# JTAG.net
KiCad netlist of a schematic drawn in Altium Designer
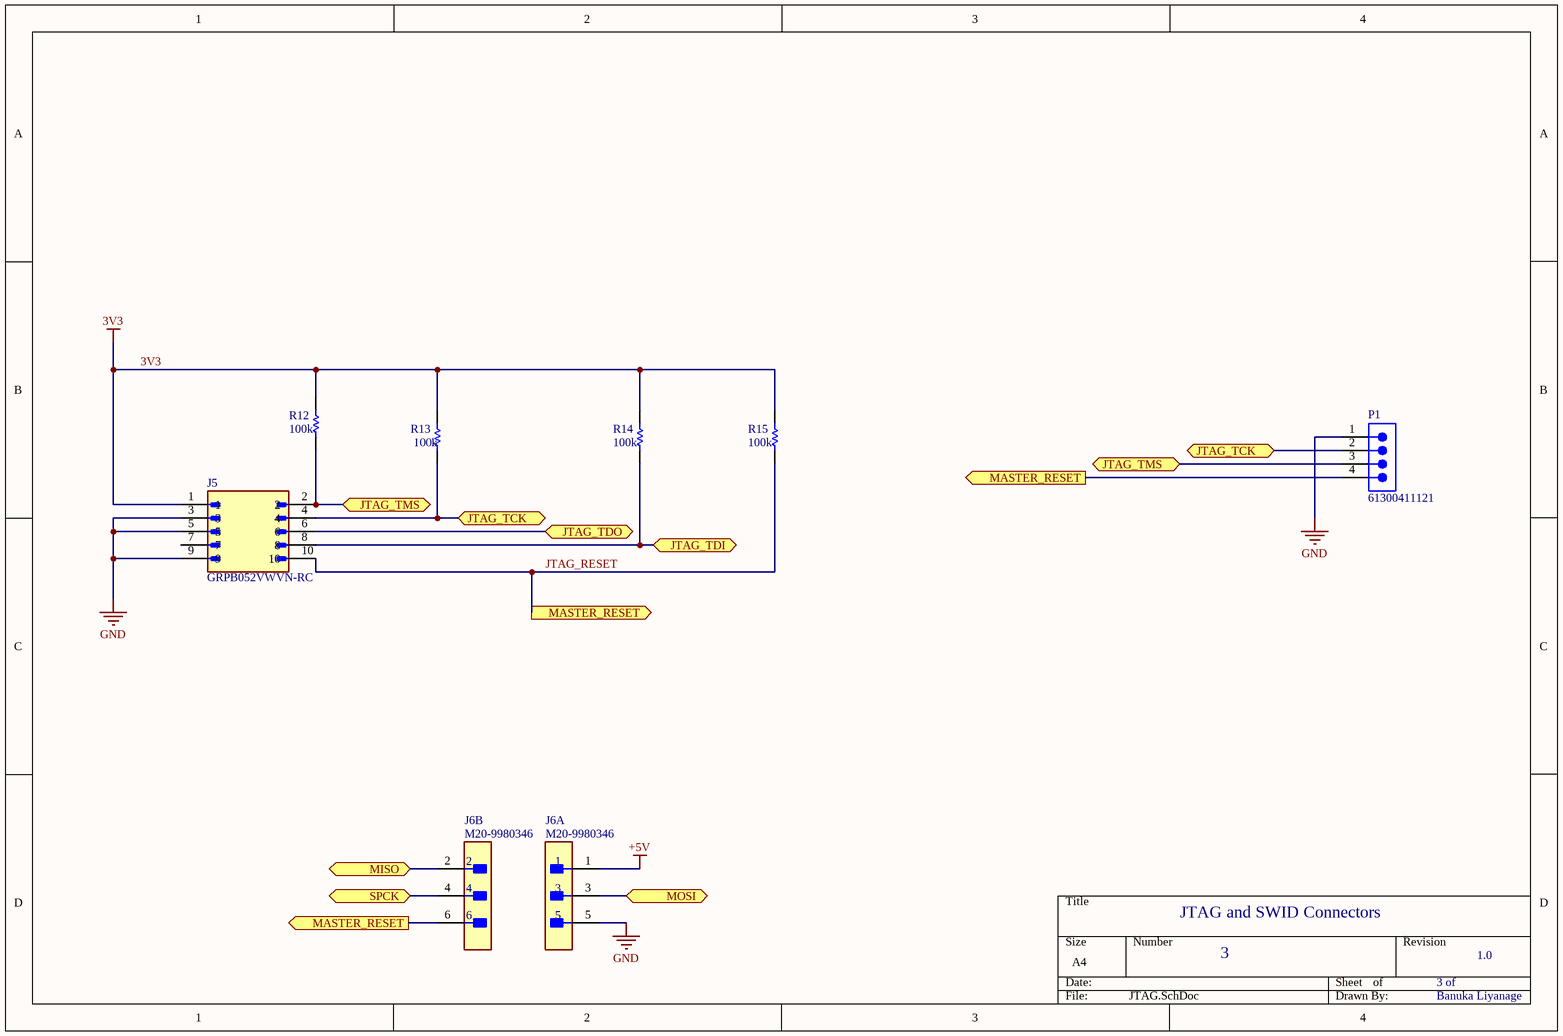
[diagram p0:  JTAG.SchDoc]

(export (version "E")
  (design (tool "Eeschema 10.0.6"))
  (components
    (comp (ref "J5")
      (value "GRPB052VWVN-RC")
      (footprint "SULLINS_GRPB052VWVN-RC")
      (description "Connector Header Through Hole 10 position 0.050 (1.27mm)")
      (fields (field (name "MF") "Sullins"))
      (libsource (lib "GRPB052VWVN-RC") (part "GRPB052VWVN-RC"))
    )
    (comp (ref "J6")
      (value "M20-9980346")
      (footprint "FP-M20-9980346-MFG")
      (description "CONN HEADER VERT 6POS 2.54MM")
      (fields
        (field (name "MANUFACTURER") "Harwin")
        (field (name "OCTOPART") "https://octopart.com/m20-9980346-harwin-5436545")
      )
      (libsource (lib "Altium Content Vault") (part "2654a11fb13586ecb194516b1c997bc"))
    )
    (comp (ref "P1")
      (value "61300411121")
      (footprint "61300411121")
      (libsource (lib "Altium Content Vault") (part "Header_Male_1R_04P"))
    )
    (comp (ref "R12")
      (value "100k")
      (footprint "RESC2013X50X30ML20T20")
      (fields (field (name "MANUFACTURER") "Vishay Dale") (field (name "PART NUMBER") "CRCW0805100KJNEA"))
      (libsource (lib "Altium Content Vault") (part "RES"))
    )
    (comp (ref "R13")
      (value "100k")
      (footprint "RESC2013X50X30ML20T20")
      (fields (field (name "MANUFACTURER") "Vishay Dale") (field (name "PART NUMBER") "CRCW0805100KJNEA"))
      (libsource (lib "Altium Content Vault") (part "RES"))
    )
    (comp (ref "R14")
      (value "100k")
      (footprint "RESC2013X50X30ML20T20")
      (fields (field (name "MANUFACTURER") "Vishay Dale") (field (name "PART NUMBER") "CRCW0805100KJNEA"))
      (libsource (lib "Altium Content Vault") (part "RES"))
    )
    (comp (ref "R15")
      (value "100k")
      (footprint "RESC2013X50X30ML20T20")
      (fields (field (name "MANUFACTURER") "Vishay Dale") (field (name "PART NUMBER") "CRCW0805100KJNEA"))
      (libsource (lib "Altium Content Vault") (part "RES"))
    )
  )
  (nets
    (net (code "1") (name "+5V") (class "Default")
      (node (ref "J6") (pin "1") (pinfunction "1_1") (pintype "passive"))
    )
    (net (code "2") (name "/JTAG_RESET") (class "Default")
      (node (ref "J5") (pin "10") (pinfunction "10_10") (pintype "passive"))
      (node (ref "J6") (pin "6") (pinfunction "6_6") (pintype "passive"))
      (node (ref "P1") (pin "4") (pinfunction "4_4") (pintype "passive"))
      (node (ref "R15") (pin "1") (pinfunction "1_1") (pintype "passive"))
    )
    (net (code "3") (name "/JTAG_TCK") (class "Default")
      (node (ref "J5") (pin "4") (pinfunction "4_4") (pintype "passive"))
      (node (ref "P1") (pin "2") (pinfunction "2_2") (pintype "passive"))
      (node (ref "R13") (pin "1") (pinfunction "1_1") (pintype "passive"))
    )
    (net (code "4") (name "/JTAG_TDI") (class "Default")
      (node (ref "J5") (pin "8") (pinfunction "8_8") (pintype "passive"))
      (node (ref "R14") (pin "1") (pinfunction "1_1") (pintype "passive"))
    )
    (net (code "5") (name "/JTAG_TDO") (class "Default")
      (node (ref "J5") (pin "6") (pinfunction "6_6") (pintype "passive"))
    )
    (net (code "6") (name "/JTAG_TMS") (class "Default")
      (node (ref "J5") (pin "2") (pinfunction "2_2") (pintype "passive"))
      (node (ref "P1") (pin "3") (pinfunction "3_3") (pintype "passive"))
      (node (ref "R12") (pin "1") (pinfunction "1_1") (pintype "passive"))
    )
    (net (code "7") (name "/MISO") (class "Default")
      (node (ref "J6") (pin "2") (pinfunction "2_2") (pintype "passive"))
    )
    (net (code "8") (name "/MOSI") (class "Default")
      (node (ref "J6") (pin "3") (pinfunction "3_3") (pintype "passive"))
    )
    (net (code "9") (name "/SPCK") (class "Default")
      (node (ref "J6") (pin "4") (pinfunction "4_4") (pintype "passive"))
    )
    (net (code "10") (name "3V3") (class "Default")
      (node (ref "J5") (pin "1") (pinfunction "1_1") (pintype "passive"))
      (node (ref "R12") (pin "2") (pinfunction "2_2") (pintype "passive"))
      (node (ref "R13") (pin "2") (pinfunction "2_2") (pintype "passive"))
      (node (ref "R14") (pin "2") (pinfunction "2_2") (pintype "passive"))
      (node (ref "R15") (pin "2") (pinfunction "2_2") (pintype "passive"))
    )
    (net (code "11") (name "GND") (class "Default")
      (node (ref "J5") (pin "3") (pinfunction "3_3") (pintype "passive"))
      (node (ref "J5") (pin "5") (pinfunction "5_5") (pintype "passive"))
      (node (ref "J5") (pin "9") (pinfunction "9_9") (pintype "passive"))
      (node (ref "J6") (pin "5") (pinfunction "5_5") (pintype "passive"))
      (node (ref "P1") (pin "1") (pinfunction "1_1") (pintype "passive"))
    )
    (net (code "12") (name "unconnected-(J5-Pad7)") (class "Default")
      (node (ref "J5") (pin "7") (pinfunction "7_7") (pintype "passive"))
    )
  )
)
